# audio_sense_board_rv1.net
KiCad netlist of a schematic drawn in EAGLE
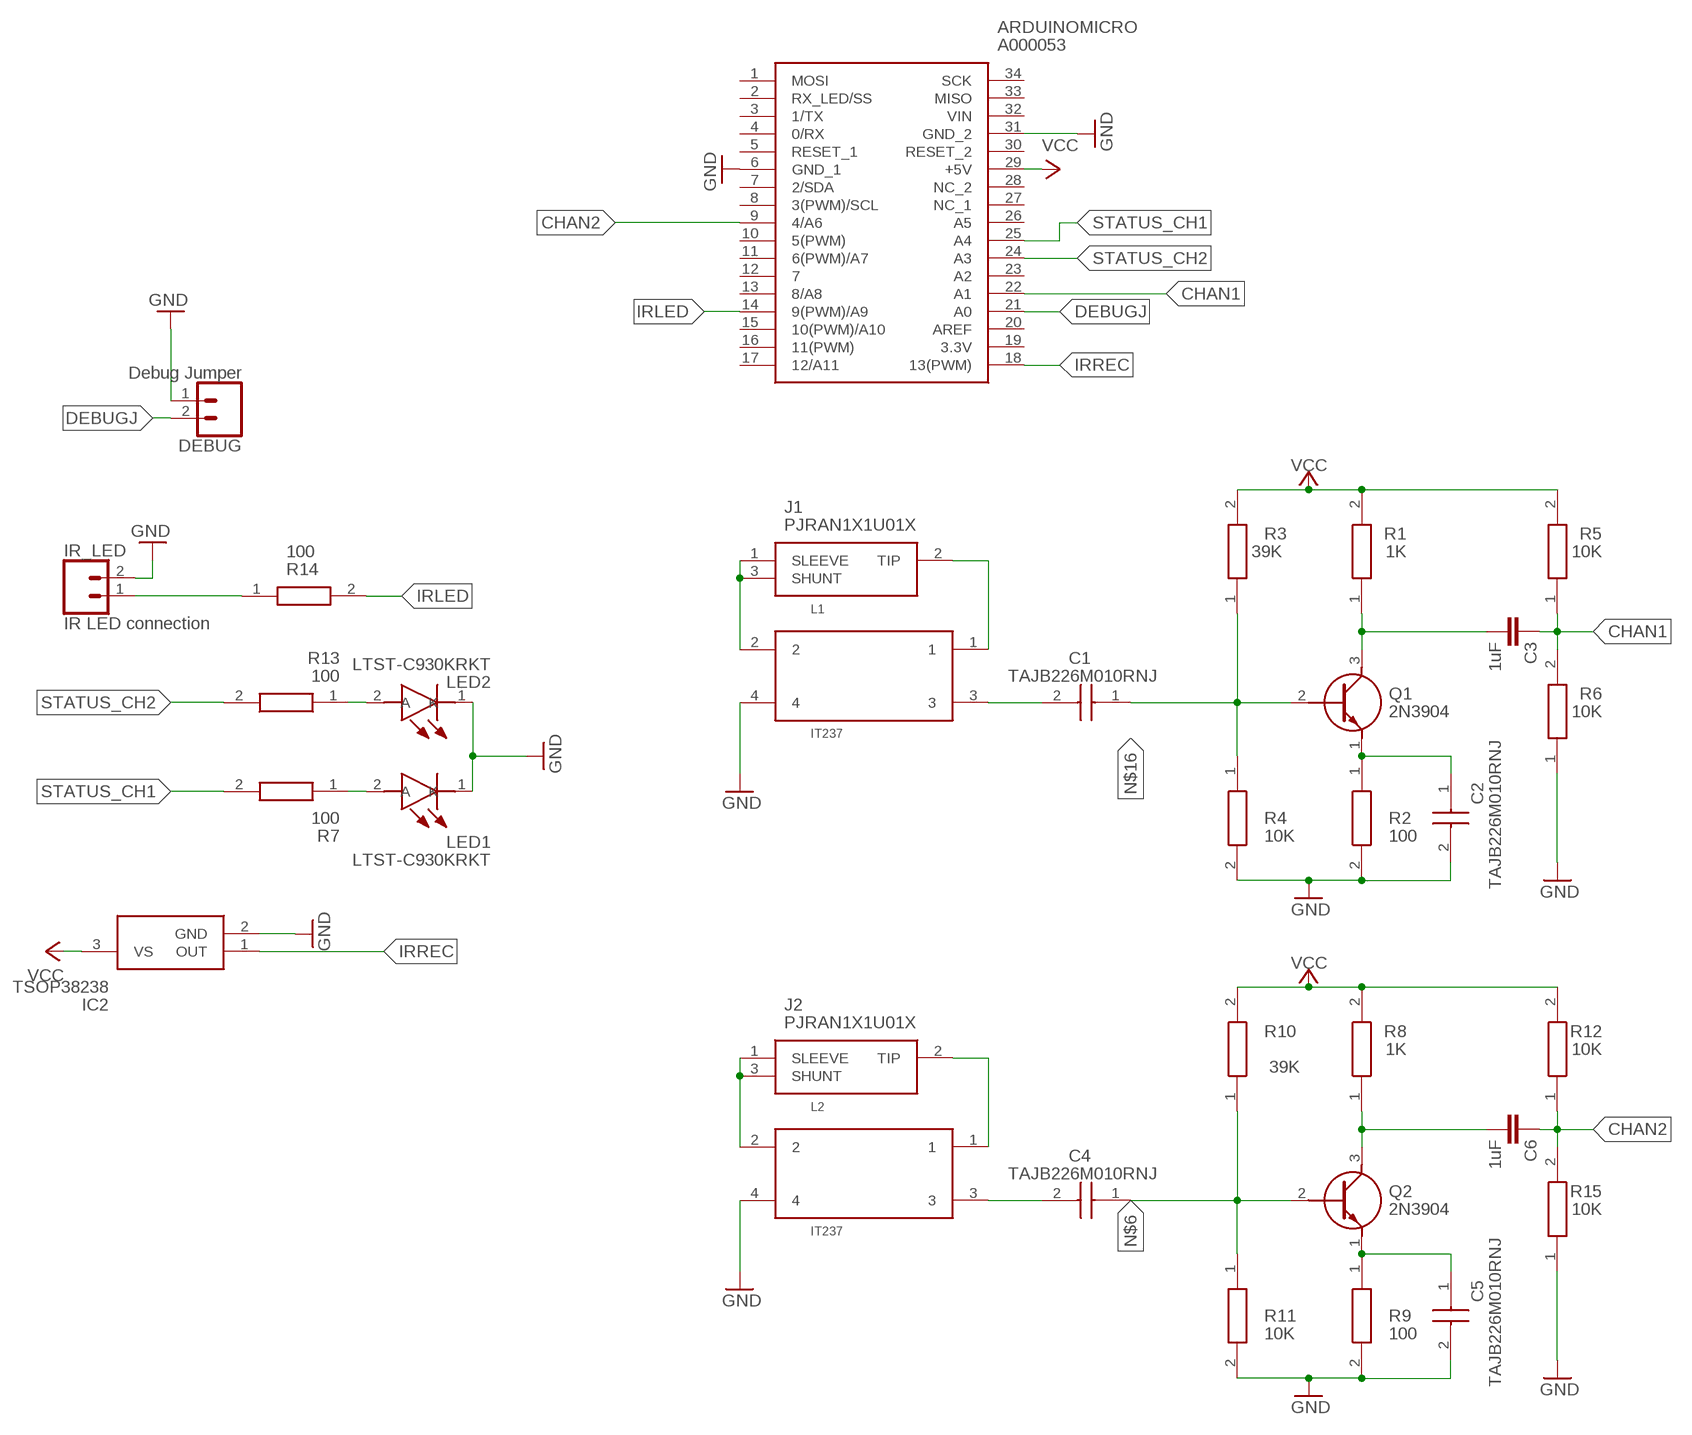
[diagram p0: schematic, sheet 1]

(export (version "E")
  (design (tool "Eeschema 10.0.6"))
  (components
    (comp (ref "ARDUINOMICRO")
      (value "A000053")
      (footprint "eagle-import:HDRV34W70P1570X254_2X17_4900X1")
      (fields (field (name "MOUSER_PART_NUMBER") "782-A000053") (field (name "RS_PART_NUMBER") "7717667"))
      (libsource (lib "eagle-import") (part "A000053"))
    )
    (comp (ref "C1")
      (value "TAJB226M010RNJ")
      (footprint "eagle-import:CAPPM3528X210N")
      (fields
        (field (name "MOUSER_PART_NUMBER") "581-TAJB226M010R")
        (field (name "RS_PART_NUMBER") "1354085")
      )
      (libsource (lib "eagle-import") (part "TAJB226M010RNJ"))
    )
    (comp (ref "C2")
      (value "TAJB226M010RNJ")
      (footprint "eagle-import:CAPPM3528X210N")
      (fields
        (field (name "MOUSER_PART_NUMBER") "581-TAJB226M010R")
        (field (name "RS_PART_NUMBER") "1354085")
      )
      (libsource (lib "eagle-import") (part "TAJB226M010RNJ"))
    )
    (comp (ref "C3")
      (value "1uF")
      (footprint "eagle-import:CAP-PTH-2.54")
      (libsource (lib "eagle-import") (part "22PF-PTH-2.54MM-200V-5%"))
    )
    (comp (ref "C4")
      (value "TAJB226M010RNJ")
      (footprint "eagle-import:CAPPM3528X210N")
      (fields
        (field (name "MOUSER_PART_NUMBER") "581-TAJB226M010R")
        (field (name "RS_PART_NUMBER") "1354085")
      )
      (libsource (lib "eagle-import") (part "TAJB226M010RNJ"))
    )
    (comp (ref "C5")
      (value "TAJB226M010RNJ")
      (footprint "eagle-import:CAPPM3528X210N")
      (fields
        (field (name "MOUSER_PART_NUMBER") "581-TAJB226M010R")
        (field (name "RS_PART_NUMBER") "1354085")
      )
      (libsource (lib "eagle-import") (part "TAJB226M010RNJ"))
    )
    (comp (ref "C6")
      (value "1uF")
      (footprint "eagle-import:CAP-PTH-2.54")
      (libsource (lib "eagle-import") (part "22PF-PTH-2.54MM-200V-5%"))
    )
    (comp (ref "DEBUG")
      (value "Debug Jumper")
      (footprint "eagle-import:1X02_LOCK")
      (libsource (lib "eagle-import") (part "CONN_02LOCK"))
    )
    (comp (ref "IC2")
      (value "TSOP38238")
      (footprint "eagle-import:TSOP38238")
      (fields (field (name "MOUSER_PART_NUMBER") "782-TSOP38238") (field (name "RS_PART_NUMBER") "8651883"))
      (libsource (lib "eagle-import") (part "TSOP38238"))
    )
    (comp (ref "IR_LED")
      (value "IR LED connection")
      (footprint "eagle-import:1X02_LOCK")
      (libsource (lib "eagle-import") (part "CONN_02LOCK"))
    )
    (comp (ref "J1")
      (value "PJRAN1X1U01X")
      (footprint "eagle-import:PJRAN1X1U01X")
      (fields (field (name "MOUSER_PART_NUMBER") "502-PJRAN1X1U01X"))
      (libsource (lib "eagle-import") (part "PJRAN1X1U01X"))
    )
    (comp (ref "J2")
      (value "PJRAN1X1U01X")
      (footprint "eagle-import:PJRAN1X1U01X")
      (fields (field (name "MOUSER_PART_NUMBER") "502-PJRAN1X1U01X"))
      (libsource (lib "eagle-import") (part "PJRAN1X1U01X"))
    )
    (comp (ref "L1")
      (value "IT237")
      (footprint "eagle-import:IT237")
      (libsource (lib "eagle-import") (part "IT237"))
    )
    (comp (ref "L2")
      (value "IT237")
      (footprint "eagle-import:IT237")
      (libsource (lib "eagle-import") (part "IT237"))
    )
    (comp (ref "LED1")
      (value "LTST-C930KRKT")
      (footprint "eagle-import:LTSTC930KRKT")
      (fields
        (field (name "MOUSER_PART_NUMBER") "859-LTST-C930KRKT")
        (field (name "RS_PART_NUMBER") "1689768")
      )
      (libsource (lib "eagle-import") (part "LTST-C930KRKT"))
    )
    (comp (ref "LED2")
      (value "LTST-C930KRKT")
      (footprint "eagle-import:LTSTC930KRKT")
      (fields
        (field (name "MOUSER_PART_NUMBER") "859-LTST-C930KRKT")
        (field (name "RS_PART_NUMBER") "1689768")
      )
      (libsource (lib "eagle-import") (part "LTST-C930KRKT"))
    )
    (comp (ref "Q1")
      (value "2N3904")
      (footprint "eagle-import:CS_TO-92")
      (fields (field (name "MOUSER_PART_NUMBER") "610-2N3904"))
      (libsource (lib "eagle-import") (part "2N3904"))
    )
    (comp (ref "Q2")
      (value "2N3904")
      (footprint "eagle-import:CS_TO-92")
      (fields (field (name "MOUSER_PART_NUMBER") "610-2N3904"))
      (libsource (lib "eagle-import") (part "2N3904"))
    )
    (comp (ref "R1")
      (value "1K")
      (footprint "eagle-import:RESC3116X70N")
      (fields
        (field (name "MANUFACTURER_PART_NUMBER") "ERJ-8GEYJ102V")
        (field (name "MOUSER_PART_NUMBER") "667-ERJ-8GEYJ102V")
      )
      (libsource (lib "eagle-import") (part "ERJ-8GEYJ102V"))
    )
    (comp (ref "R2")
      (value "100")
      (footprint "eagle-import:RESC3116X70N")
      (fields (field (name "MANUFACTURER_PART_NUMBER") "ERJ8GEYJ101V"))
      (libsource (lib "eagle-import") (part "ERJ8GEYJ101V"))
    )
    (comp (ref "R3")
      (value "39K")
      (footprint "eagle-import:RESC3116X70N")
      (fields (field (name "MANUFACTURER_PART_NUMBER") "ERJ8GEYJ101V"))
      (libsource (lib "eagle-import") (part "ERJ8GEYJ101V"))
    )
    (comp (ref "R4")
      (value "10K")
      (footprint "eagle-import:RESC3116X70N")
      (fields (field (name "MANUFACTURER_PART_NUMBER") "ERJ8GEYJ101V"))
      (libsource (lib "eagle-import") (part "ERJ8GEYJ101V"))
    )
    (comp (ref "R5")
      (value "10K")
      (footprint "eagle-import:RESC3116X70N")
      (fields (field (name "MANUFACTURER_PART_NUMBER") "ERJ8GEYJ101V"))
      (libsource (lib "eagle-import") (part "ERJ8GEYJ101V"))
    )
    (comp (ref "R6")
      (value "10K")
      (footprint "eagle-import:RESC3116X70N")
      (fields (field (name "MANUFACTURER_PART_NUMBER") "ERJ8GEYJ101V"))
      (libsource (lib "eagle-import") (part "ERJ8GEYJ101V"))
    )
    (comp (ref "R7")
      (value "100")
      (footprint "eagle-import:RESC3116X70N")
      (fields (field (name "MANUFACTURER_PART_NUMBER") "ERJ8GEYJ101V"))
      (libsource (lib "eagle-import") (part "ERJ8GEYJ101V"))
    )
    (comp (ref "R8")
      (value "1K")
      (footprint "eagle-import:RESC3116X70N")
      (fields
        (field (name "MANUFACTURER_PART_NUMBER") "ERJ-8GEYJ102V")
        (field (name "MOUSER_PART_NUMBER") "667-ERJ-8GEYJ102V")
      )
      (libsource (lib "eagle-import") (part "ERJ-8GEYJ102V"))
    )
    (comp (ref "R9")
      (value "100")
      (footprint "eagle-import:RESC3116X70N")
      (fields (field (name "MANUFACTURER_PART_NUMBER") "ERJ8GEYJ101V"))
      (libsource (lib "eagle-import") (part "ERJ8GEYJ101V"))
    )
    (comp (ref "R10")
      (value "39K")
      (footprint "eagle-import:RESC3116X70N")
      (fields (field (name "MANUFACTURER_PART_NUMBER") "ERJ8GEYJ101V"))
      (libsource (lib "eagle-import") (part "ERJ8GEYJ101V"))
    )
    (comp (ref "R11")
      (value "10K")
      (footprint "eagle-import:RESC3116X70N")
      (fields (field (name "MANUFACTURER_PART_NUMBER") "ERJ8GEYJ101V"))
      (libsource (lib "eagle-import") (part "ERJ8GEYJ101V"))
    )
    (comp (ref "R12")
      (value "10K")
      (footprint "eagle-import:RESC3116X70N")
      (fields (field (name "MANUFACTURER_PART_NUMBER") "ERJ8GEYJ101V"))
      (libsource (lib "eagle-import") (part "ERJ8GEYJ101V"))
    )
    (comp (ref "R13")
      (value "100")
      (footprint "eagle-import:RESC3116X70N")
      (fields (field (name "MANUFACTURER_PART_NUMBER") "ERJ8GEYJ101V"))
      (libsource (lib "eagle-import") (part "ERJ8GEYJ101V"))
    )
    (comp (ref "R14")
      (value "100")
      (footprint "eagle-import:RESC3116X70N")
      (fields (field (name "MANUFACTURER_PART_NUMBER") "ERJ8GEYJ101V"))
      (libsource (lib "eagle-import") (part "ERJ8GEYJ101V"))
    )
    (comp (ref "R15")
      (value "10K")
      (footprint "eagle-import:RESC3116X70N")
      (fields (field (name "MANUFACTURER_PART_NUMBER") "ERJ8GEYJ101V"))
      (libsource (lib "eagle-import") (part "ERJ8GEYJ101V"))
    )
  )
  (nets
    (net (code "1") (name "CHAN1") (class "Default")
      (node (ref "ARDUINOMICRO") (pin "22") (pinfunction "A1_22") (pintype "bidirectional"))
      (node (ref "C3") (pin "1") (pinfunction "1_1") (pintype "passive"))
      (node (ref "R5") (pin "1") (pinfunction "1_1") (pintype "bidirectional"))
      (node (ref "R6") (pin "2") (pinfunction "2_2") (pintype "bidirectional"))
    )
    (net (code "2") (name "CHAN2") (class "Default")
      (node (ref "ARDUINOMICRO") (pin "9") (pinfunction "4/A6_9") (pintype "bidirectional"))
      (node (ref "C6") (pin "1") (pinfunction "1_1") (pintype "passive"))
      (node (ref "R12") (pin "1") (pinfunction "1_1") (pintype "bidirectional"))
      (node (ref "R15") (pin "2") (pinfunction "2_2") (pintype "bidirectional"))
    )
    (net (code "3") (name "DEBUGJ") (class "Default")
      (node (ref "ARDUINOMICRO") (pin "21") (pinfunction "A0_21") (pintype "bidirectional"))
      (node (ref "DEBUG") (pin "2") (pinfunction "2_2") (pintype "passive"))
    )
    (net (code "4") (name "GND") (class "Default")
      (node (ref "ARDUINOMICRO") (pin "31") (pinfunction "GND_2_31") (pintype "bidirectional"))
      (node (ref "ARDUINOMICRO") (pin "6") (pinfunction "GND_1_6") (pintype "power_in"))
      (node (ref "C2") (pin "2") (pinfunction "-_2") (pintype "bidirectional"))
      (node (ref "C5") (pin "2") (pinfunction "-_2") (pintype "bidirectional"))
      (node (ref "DEBUG") (pin "1") (pinfunction "1_1") (pintype "passive"))
      (node (ref "IC2") (pin "2") (pinfunction "GND_2") (pintype "bidirectional"))
      (node (ref "IR_LED") (pin "2") (pinfunction "2_2") (pintype "passive"))
      (node (ref "L1") (pin "4") (pinfunction "4_4") (pintype "bidirectional"))
      (node (ref "L2") (pin "4") (pinfunction "4_4") (pintype "bidirectional"))
      (node (ref "LED1") (pin "1") (pinfunction "K_1") (pintype "bidirectional"))
      (node (ref "LED2") (pin "1") (pinfunction "K_1") (pintype "bidirectional"))
      (node (ref "R11") (pin "2") (pinfunction "2_2") (pintype "bidirectional"))
      (node (ref "R15") (pin "1") (pinfunction "1_1") (pintype "bidirectional"))
      (node (ref "R2") (pin "2") (pinfunction "2_2") (pintype "bidirectional"))
      (node (ref "R4") (pin "2") (pinfunction "2_2") (pintype "bidirectional"))
      (node (ref "R6") (pin "1") (pinfunction "1_1") (pintype "bidirectional"))
      (node (ref "R9") (pin "2") (pinfunction "2_2") (pintype "bidirectional"))
    )
    (net (code "5") (name "IRLED") (class "Default")
      (node (ref "ARDUINOMICRO") (pin "14") (pinfunction "9(PWM)/A9_14") (pintype "bidirectional"))
      (node (ref "R14") (pin "2") (pinfunction "2_2") (pintype "bidirectional"))
    )
    (net (code "6") (name "IRREC") (class "Default")
      (node (ref "ARDUINOMICRO") (pin "18") (pinfunction "13(PWM)_18") (pintype "bidirectional"))
      (node (ref "IC2") (pin "1") (pinfunction "OUT_1") (pintype "bidirectional"))
    )
    (net (code "7") (name "N$6") (class "Default")
      (node (ref "C4") (pin "1") (pinfunction "+_1") (pintype "bidirectional"))
      (node (ref "Q2") (pin "2") (pinfunction "B_2") (pintype "bidirectional"))
      (node (ref "R10") (pin "1") (pinfunction "1_1") (pintype "bidirectional"))
      (node (ref "R11") (pin "1") (pinfunction "1_1") (pintype "bidirectional"))
    )
    (net (code "8") (name "N$16") (class "Default")
      (node (ref "C1") (pin "1") (pinfunction "+_1") (pintype "bidirectional"))
      (node (ref "Q1") (pin "2") (pinfunction "B_2") (pintype "bidirectional"))
      (node (ref "R3") (pin "1") (pinfunction "1_1") (pintype "bidirectional"))
      (node (ref "R4") (pin "1") (pinfunction "1_1") (pintype "bidirectional"))
    )
    (net (code "9") (name "Net-(C1--)") (class "Default")
      (node (ref "C1") (pin "2") (pinfunction "-_2") (pintype "bidirectional"))
      (node (ref "L1") (pin "3") (pinfunction "3_3") (pintype "bidirectional"))
    )
    (net (code "10") (name "Net-(C2-+)") (class "Default")
      (node (ref "C2") (pin "1") (pinfunction "+_1") (pintype "bidirectional"))
      (node (ref "Q1") (pin "1") (pinfunction "E_1") (pintype "bidirectional"))
      (node (ref "R2") (pin "1") (pinfunction "1_1") (pintype "bidirectional"))
    )
    (net (code "11") (name "Net-(C4--)") (class "Default")
      (node (ref "C4") (pin "2") (pinfunction "-_2") (pintype "bidirectional"))
      (node (ref "L2") (pin "3") (pinfunction "3_3") (pintype "bidirectional"))
    )
    (net (code "12") (name "Net-(C5-+)") (class "Default")
      (node (ref "C5") (pin "1") (pinfunction "+_1") (pintype "bidirectional"))
      (node (ref "Q2") (pin "1") (pinfunction "E_1") (pintype "bidirectional"))
      (node (ref "R9") (pin "1") (pinfunction "1_1") (pintype "bidirectional"))
    )
    (net (code "13") (name "Net-(IR_LED-Pad1)") (class "Default")
      (node (ref "IR_LED") (pin "1") (pinfunction "1_1") (pintype "passive"))
      (node (ref "R14") (pin "1") (pinfunction "1_1") (pintype "bidirectional"))
    )
    (net (code "14") (name "Net-(J1-SHUNT)") (class "Default")
      (node (ref "J1") (pin "1") (pinfunction "SLEEVE_1") (pintype "bidirectional"))
      (node (ref "J1") (pin "3") (pinfunction "SHUNT_3") (pintype "bidirectional"))
      (node (ref "L1") (pin "2") (pinfunction "2_2") (pintype "bidirectional"))
    )
    (net (code "15") (name "Net-(J1-TIP)") (class "Default")
      (node (ref "J1") (pin "2") (pinfunction "TIP_2") (pintype "bidirectional"))
      (node (ref "L1") (pin "1") (pinfunction "1_1") (pintype "bidirectional"))
    )
    (net (code "16") (name "Net-(J2-SHUNT)") (class "Default")
      (node (ref "J2") (pin "1") (pinfunction "SLEEVE_1") (pintype "bidirectional"))
      (node (ref "J2") (pin "3") (pinfunction "SHUNT_3") (pintype "bidirectional"))
      (node (ref "L2") (pin "2") (pinfunction "2_2") (pintype "bidirectional"))
    )
    (net (code "17") (name "Net-(J2-TIP)") (class "Default")
      (node (ref "J2") (pin "2") (pinfunction "TIP_2") (pintype "bidirectional"))
      (node (ref "L2") (pin "1") (pinfunction "1_1") (pintype "bidirectional"))
    )
    (net (code "18") (name "Net-(LED1-A)") (class "Default")
      (node (ref "LED1") (pin "2") (pinfunction "A_2") (pintype "bidirectional"))
      (node (ref "R7") (pin "1") (pinfunction "1_1") (pintype "bidirectional"))
    )
    (net (code "19") (name "Net-(LED2-A)") (class "Default")
      (node (ref "LED2") (pin "2") (pinfunction "A_2") (pintype "bidirectional"))
      (node (ref "R13") (pin "1") (pinfunction "1_1") (pintype "bidirectional"))
    )
    (net (code "20") (name "Net-(Q1-C)") (class "Default")
      (node (ref "C3") (pin "2") (pinfunction "2_2") (pintype "passive"))
      (node (ref "Q1") (pin "3") (pinfunction "C_3") (pintype "bidirectional"))
      (node (ref "R1") (pin "1") (pinfunction "1_1") (pintype "bidirectional"))
    )
    (net (code "21") (name "Net-(Q2-C)") (class "Default")
      (node (ref "C6") (pin "2") (pinfunction "2_2") (pintype "passive"))
      (node (ref "Q2") (pin "3") (pinfunction "C_3") (pintype "bidirectional"))
      (node (ref "R8") (pin "1") (pinfunction "1_1") (pintype "bidirectional"))
    )
    (net (code "22") (name "STATUS_CH1") (class "Default")
      (node (ref "ARDUINOMICRO") (pin "25") (pinfunction "A4_25") (pintype "bidirectional"))
      (node (ref "R7") (pin "2") (pinfunction "2_2") (pintype "bidirectional"))
    )
    (net (code "23") (name "STATUS_CH2") (class "Default")
      (node (ref "ARDUINOMICRO") (pin "24") (pinfunction "A3_24") (pintype "bidirectional"))
      (node (ref "R13") (pin "2") (pinfunction "2_2") (pintype "bidirectional"))
    )
    (net (code "24") (name "VCC") (class "Default")
      (node (ref "ARDUINOMICRO") (pin "29") (pinfunction "+5V_29") (pintype "bidirectional"))
      (node (ref "IC2") (pin "3") (pinfunction "VS_3") (pintype "bidirectional"))
      (node (ref "R1") (pin "2") (pinfunction "2_2") (pintype "bidirectional"))
      (node (ref "R10") (pin "2") (pinfunction "2_2") (pintype "bidirectional"))
      (node (ref "R12") (pin "2") (pinfunction "2_2") (pintype "bidirectional"))
      (node (ref "R3") (pin "2") (pinfunction "2_2") (pintype "bidirectional"))
      (node (ref "R5") (pin "2") (pinfunction "2_2") (pintype "bidirectional"))
      (node (ref "R8") (pin "2") (pinfunction "2_2") (pintype "bidirectional"))
    )
    (net (code "25") (name "unconnected-(ARDUINOMICRO-0{slash}RX-Pad4)") (class "Default")
      (node (ref "ARDUINOMICRO") (pin "4") (pinfunction "0/RX_4") (pintype "bidirectional"))
    )
    (net (code "26") (name "unconnected-(ARDUINOMICRO-1{slash}TX-Pad3)") (class "Default")
      (node (ref "ARDUINOMICRO") (pin "3") (pinfunction "1/TX_3") (pintype "bidirectional"))
    )
    (net (code "27") (name "unconnected-(ARDUINOMICRO-2{slash}SDA-Pad7)") (class "Default")
      (node (ref "ARDUINOMICRO") (pin "7") (pinfunction "2/SDA_7") (pintype "bidirectional"))
    )
    (net (code "28") (name "unconnected-(ARDUINOMICRO-3(PWM){slash}SCL-Pad8)") (class "Default")
      (node (ref "ARDUINOMICRO") (pin "8") (pinfunction "3(PWM)/SCL_8") (pintype "bidirectional"))
    )
    (net (code "29") (name "unconnected-(ARDUINOMICRO-3.3V-Pad19)") (class "Default")
      (node (ref "ARDUINOMICRO") (pin "19") (pinfunction "3.3V_19") (pintype "bidirectional"))
    )
    (net (code "30") (name "unconnected-(ARDUINOMICRO-5(PWM)-Pad10)") (class "Default")
      (node (ref "ARDUINOMICRO") (pin "10") (pinfunction "5(PWM)_10") (pintype "bidirectional"))
    )
    (net (code "31") (name "unconnected-(ARDUINOMICRO-6(PWM){slash}A7-Pad11)") (class "Default")
      (node (ref "ARDUINOMICRO") (pin "11") (pinfunction "6(PWM)/A7_11") (pintype "bidirectional"))
    )
    (net (code "32") (name "unconnected-(ARDUINOMICRO-7-Pad12)") (class "Default")
      (node (ref "ARDUINOMICRO") (pin "12") (pinfunction "7_12") (pintype "bidirectional"))
    )
    (net (code "33") (name "unconnected-(ARDUINOMICRO-8{slash}A8-Pad13)") (class "Default")
      (node (ref "ARDUINOMICRO") (pin "13") (pinfunction "8/A8_13") (pintype "bidirectional"))
    )
    (net (code "34") (name "unconnected-(ARDUINOMICRO-10(PWM){slash}A10-Pad15)") (class "Default")
      (node (ref "ARDUINOMICRO") (pin "15") (pinfunction "10(PWM)/A10_15") (pintype "bidirectional"))
    )
    (net (code "35") (name "unconnected-(ARDUINOMICRO-11(PWM)-Pad16)") (class "Default")
      (node (ref "ARDUINOMICRO") (pin "16") (pinfunction "11(PWM)_16") (pintype "bidirectional"))
    )
    (net (code "36") (name "unconnected-(ARDUINOMICRO-12{slash}A11-Pad17)") (class "Default")
      (node (ref "ARDUINOMICRO") (pin "17") (pinfunction "12/A11_17") (pintype "bidirectional"))
    )
    (net (code "37") (name "unconnected-(ARDUINOMICRO-A2-Pad23)") (class "Default")
      (node (ref "ARDUINOMICRO") (pin "23") (pinfunction "A2_23") (pintype "bidirectional"))
    )
    (net (code "38") (name "unconnected-(ARDUINOMICRO-A5-Pad26)") (class "Default")
      (node (ref "ARDUINOMICRO") (pin "26") (pinfunction "A5_26") (pintype "bidirectional"))
    )
    (net (code "39") (name "unconnected-(ARDUINOMICRO-AREF-Pad20)") (class "Default")
      (node (ref "ARDUINOMICRO") (pin "20") (pinfunction "AREF_20") (pintype "bidirectional"))
    )
    (net (code "40") (name "unconnected-(ARDUINOMICRO-MISO-Pad33)") (class "Default")
      (node (ref "ARDUINOMICRO") (pin "33") (pinfunction "MISO_33") (pintype "bidirectional"))
    )
    (net (code "41") (name "unconnected-(ARDUINOMICRO-MOSI-Pad1)") (class "Default")
      (node (ref "ARDUINOMICRO") (pin "1") (pinfunction "MOSI_1") (pintype "bidirectional"))
    )
    (net (code "42") (name "unconnected-(ARDUINOMICRO-NC_1-Pad27)") (class "Default")
      (node (ref "ARDUINOMICRO") (pin "27") (pinfunction "NC_1_27") (pintype "bidirectional"))
    )
    (net (code "43") (name "unconnected-(ARDUINOMICRO-NC_2-Pad28)") (class "Default")
      (node (ref "ARDUINOMICRO") (pin "28") (pinfunction "NC_2_28") (pintype "bidirectional"))
    )
    (net (code "44") (name "unconnected-(ARDUINOMICRO-RESET_1-Pad5)") (class "Default")
      (node (ref "ARDUINOMICRO") (pin "5") (pinfunction "RESET_1_5") (pintype "bidirectional"))
    )
    (net (code "45") (name "unconnected-(ARDUINOMICRO-RESET_2-Pad30)") (class "Default")
      (node (ref "ARDUINOMICRO") (pin "30") (pinfunction "RESET_2_30") (pintype "bidirectional"))
    )
    (net (code "46") (name "unconnected-(ARDUINOMICRO-RX_LED{slash}SS-Pad2)") (class "Default")
      (node (ref "ARDUINOMICRO") (pin "2") (pinfunction "RX_LED/SS_2") (pintype "bidirectional"))
    )
    (net (code "47") (name "unconnected-(ARDUINOMICRO-SCK-Pad34)") (class "Default")
      (node (ref "ARDUINOMICRO") (pin "34") (pinfunction "SCK_34") (pintype "bidirectional"))
    )
    (net (code "48") (name "unconnected-(ARDUINOMICRO-VIN-Pad32)") (class "Default")
      (node (ref "ARDUINOMICRO") (pin "32") (pinfunction "VIN_32") (pintype "bidirectional"))
    )
  )
)
